# PDM.net
KiCad netlist of a schematic drawn in EAGLE
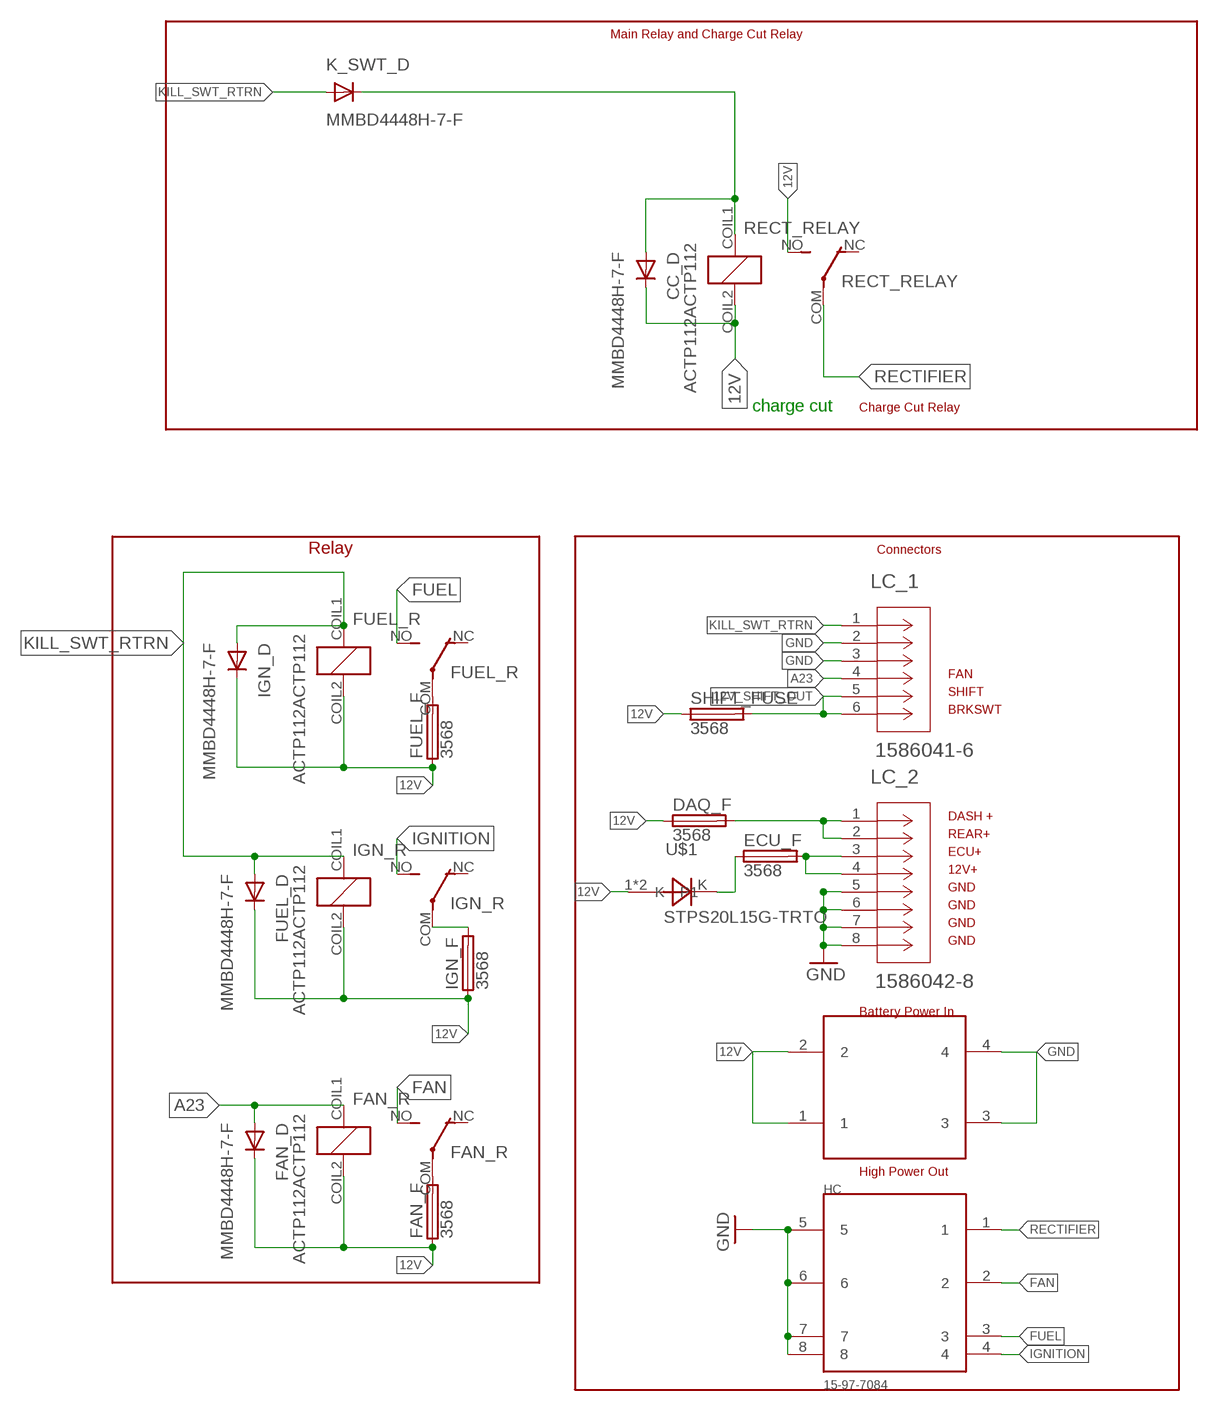
[diagram p0: schematic, sheet 1]

(export (version "E")
  (design (tool "Eeschema 10.0.6"))
  (components
    (comp (ref "BAT_SUP")
      (value "15-97-8043")
      (footprint "eagle-import:15-97-8043")
      (libsource (lib "eagle-import") (part "15-97-8043"))
    )
    (comp (ref "CC_D")
      (value "MMBD4448H-7-F")
      (footprint "eagle-import:SOT23-3")
      (libsource (lib "eagle-import") (part "MMBD4448H-7-F"))
    )
    (comp (ref "DAQ_F")
      (value "3568")
      (footprint "eagle-import:3568")
      (libsource (lib "eagle-import") (part "3568"))
    )
    (comp (ref "ECU_F")
      (value "3568")
      (footprint "eagle-import:3568")
      (libsource (lib "eagle-import") (part "3568"))
    )
    (comp (ref "FAN_D")
      (value "MMBD4448H-7-F")
      (footprint "eagle-import:SOT23-3")
      (libsource (lib "eagle-import") (part "MMBD4448H-7-F"))
    )
    (comp (ref "FAN_F")
      (value "3568")
      (footprint "eagle-import:3568")
      (libsource (lib "eagle-import") (part "3568"))
    )
    (comp (ref "FAN_R")
      (value "ACTP112ACTP112")
      (footprint "eagle-import:ACTP112")
      (libsource (lib "eagle-import") (part "ACTP112ACTP112"))
    )
    (comp (ref "FUEL_D")
      (value "MMBD4448H-7-F")
      (footprint "eagle-import:SOT23-3")
      (libsource (lib "eagle-import") (part "MMBD4448H-7-F"))
    )
    (comp (ref "FUEL_F")
      (value "3568")
      (footprint "eagle-import:3568")
      (libsource (lib "eagle-import") (part "3568"))
    )
    (comp (ref "FUEL_R")
      (value "ACTP112ACTP112")
      (footprint "eagle-import:ACTP112")
      (libsource (lib "eagle-import") (part "ACTP112ACTP112"))
    )
    (comp (ref "HC")
      (value "15-97-7084")
      (footprint "eagle-import:15-97-7084")
      (libsource (lib "eagle-import") (part "15-97-7084"))
    )
    (comp (ref "IGN_D")
      (value "MMBD4448H-7-F")
      (footprint "eagle-import:SOT23-3")
      (libsource (lib "eagle-import") (part "MMBD4448H-7-F"))
    )
    (comp (ref "IGN_F")
      (value "3568")
      (footprint "eagle-import:3568")
      (libsource (lib "eagle-import") (part "3568"))
    )
    (comp (ref "IGN_R")
      (value "ACTP112ACTP112")
      (footprint "eagle-import:ACTP112")
      (libsource (lib "eagle-import") (part "ACTP112ACTP112"))
    )
    (comp (ref "K_SWT_D")
      (value "MMBD4448H-7-F")
      (footprint "eagle-import:SOT23-3")
      (libsource (lib "eagle-import") (part "MMBD4448H-7-F"))
    )
    (comp (ref "LC_1")
      (value "1586041-6")
      (footprint "eagle-import:1586041-6")
      (libsource (lib "eagle-import") (part "1586041-6"))
    )
    (comp (ref "LC_2")
      (value "1586042-8")
      (footprint "eagle-import:1586042-8")
      (libsource (lib "eagle-import") (part "1586042-8"))
    )
    (comp (ref "RECT_RELAY")
      (value "ACTP112ACTP112")
      (footprint "eagle-import:ACTP112")
      (libsource (lib "eagle-import") (part "ACTP112ACTP112"))
    )
    (comp (ref "SHIFT_FUSE")
      (value "3568")
      (footprint "eagle-import:3568")
      (libsource (lib "eagle-import") (part "3568"))
    )
    (comp (ref "U$1")
      (value "STPS20L15G-TRTO")
      (footprint "eagle-import:TO-262DIODE")
      (libsource (lib "eagle-import") (part "STPS20L15G-TRTO"))
    )
  )
  (nets
    (net (code "1") (name "12V") (class "Default")
      (node (ref "BAT_SUP") (pin "1") (pinfunction "1_1") (pintype "bidirectional"))
      (node (ref "BAT_SUP") (pin "2") (pinfunction "2_2") (pintype "bidirectional"))
      (node (ref "CC_D") (pin "3") (pinfunction "C_3") (pintype "passive"))
      (node (ref "DAQ_F") (pin "1") (pinfunction "1_1") (pintype "passive"))
      (node (ref "DAQ_F") (pin "2") (pinfunction "1_2") (pintype "passive"))
      (node (ref "FAN_D") (pin "3") (pinfunction "C_3") (pintype "passive"))
      (node (ref "FAN_F") (pin "1") (pinfunction "1_1") (pintype "passive"))
      (node (ref "FAN_F") (pin "2") (pinfunction "1_2") (pintype "passive"))
      (node (ref "FAN_R") (pin "COIL2") (pinfunction "COIL2_COIL2") (pintype "passive"))
      (node (ref "FUEL_D") (pin "3") (pinfunction "C_3") (pintype "passive"))
      (node (ref "FUEL_F") (pin "1") (pinfunction "1_1") (pintype "passive"))
      (node (ref "FUEL_F") (pin "2") (pinfunction "1_2") (pintype "passive"))
      (node (ref "FUEL_R") (pin "COIL2") (pinfunction "COIL2_COIL2") (pintype "passive"))
      (node (ref "IGN_D") (pin "3") (pinfunction "C_3") (pintype "passive"))
      (node (ref "IGN_F") (pin "1") (pinfunction "1_1") (pintype "passive"))
      (node (ref "IGN_F") (pin "2") (pinfunction "1_2") (pintype "passive"))
      (node (ref "IGN_R") (pin "COIL2") (pinfunction "COIL2_COIL2") (pintype "passive"))
      (node (ref "RECT_RELAY") (pin "COIL2") (pinfunction "COIL2_COIL2") (pintype "passive"))
      (node (ref "RECT_RELAY") (pin "NO") (pinfunction "NO_NO") (pintype "passive"))
      (node (ref "SHIFT_FUSE") (pin "1") (pinfunction "1_1") (pintype "passive"))
      (node (ref "SHIFT_FUSE") (pin "2") (pinfunction "1_2") (pintype "passive"))
      (node (ref "U$1") (pin "1") (pinfunction "P1_1") (pintype "bidirectional"))
      (node (ref "U$1") (pin "2") (pinfunction "P1_2") (pintype "bidirectional"))
    )
    (net (code "2") (name "12V_SHIFT_OUT") (class "Default")
      (node (ref "LC_1") (pin "5") (pinfunction "5_5") (pintype "passive"))
      (node (ref "LC_1") (pin "6") (pinfunction "6_6") (pintype "passive"))
      (node (ref "SHIFT_FUSE") (pin "3") (pinfunction "2_3") (pintype "passive"))
      (node (ref "SHIFT_FUSE") (pin "4") (pinfunction "2_4") (pintype "passive"))
    )
    (net (code "3") (name "A23") (class "Default")
      (node (ref "FAN_D") (pin "1") (pinfunction "A_1") (pintype "passive"))
      (node (ref "FAN_R") (pin "COIL1") (pinfunction "COIL1_COIL1") (pintype "passive"))
      (node (ref "LC_1") (pin "4") (pinfunction "4_4") (pintype "passive"))
    )
    (net (code "4") (name "FAN") (class "Default")
      (node (ref "FAN_R") (pin "NO") (pinfunction "NO_NO") (pintype "passive"))
      (node (ref "HC") (pin "2") (pinfunction "2_2") (pintype "bidirectional"))
    )
    (net (code "5") (name "FUEL") (class "Default")
      (node (ref "FUEL_R") (pin "NO") (pinfunction "NO_NO") (pintype "passive"))
      (node (ref "HC") (pin "3") (pinfunction "3_3") (pintype "bidirectional"))
    )
    (net (code "6") (name "GND") (class "Default")
      (node (ref "BAT_SUP") (pin "3") (pinfunction "3_3") (pintype "bidirectional"))
      (node (ref "BAT_SUP") (pin "4") (pinfunction "4_4") (pintype "bidirectional"))
      (node (ref "HC") (pin "5") (pinfunction "5_5") (pintype "bidirectional"))
      (node (ref "HC") (pin "6") (pinfunction "6_6") (pintype "bidirectional"))
      (node (ref "HC") (pin "7") (pinfunction "7_7") (pintype "bidirectional"))
      (node (ref "HC") (pin "8") (pinfunction "8_8") (pintype "bidirectional"))
      (node (ref "LC_1") (pin "2") (pinfunction "2_2") (pintype "passive"))
      (node (ref "LC_1") (pin "3") (pinfunction "3_3") (pintype "passive"))
      (node (ref "LC_2") (pin "5") (pinfunction "5_5") (pintype "passive"))
      (node (ref "LC_2") (pin "6") (pinfunction "6_6") (pintype "passive"))
      (node (ref "LC_2") (pin "7") (pinfunction "7_7") (pintype "passive"))
      (node (ref "LC_2") (pin "8") (pinfunction "8_8") (pintype "passive"))
    )
    (net (code "7") (name "IGNITION") (class "Default")
      (node (ref "HC") (pin "4") (pinfunction "4_4") (pintype "bidirectional"))
      (node (ref "IGN_R") (pin "NO") (pinfunction "NO_NO") (pintype "passive"))
    )
    (net (code "8") (name "KILL_SWT_RTRN") (class "Default")
      (node (ref "FUEL_D") (pin "1") (pinfunction "A_1") (pintype "passive"))
      (node (ref "FUEL_R") (pin "COIL1") (pinfunction "COIL1_COIL1") (pintype "passive"))
      (node (ref "IGN_D") (pin "1") (pinfunction "A_1") (pintype "passive"))
      (node (ref "IGN_R") (pin "COIL1") (pinfunction "COIL1_COIL1") (pintype "passive"))
      (node (ref "K_SWT_D") (pin "1") (pinfunction "A_1") (pintype "passive"))
      (node (ref "LC_1") (pin "1") (pinfunction "1_1") (pintype "passive"))
    )
    (net (code "9") (name "Net-(CC_D-A)") (class "Default")
      (node (ref "CC_D") (pin "1") (pinfunction "A_1") (pintype "passive"))
      (node (ref "K_SWT_D") (pin "3") (pinfunction "C_3") (pintype "passive"))
      (node (ref "RECT_RELAY") (pin "COIL1") (pinfunction "COIL1_COIL1") (pintype "passive"))
    )
    (net (code "10") (name "Net-(DAQ_F-2-Pad3)") (class "Default")
      (node (ref "DAQ_F") (pin "3") (pinfunction "2_3") (pintype "passive"))
      (node (ref "DAQ_F") (pin "4") (pinfunction "2_4") (pintype "passive"))
      (node (ref "LC_2") (pin "1") (pinfunction "1_1") (pintype "passive"))
      (node (ref "LC_2") (pin "2") (pinfunction "2_2") (pintype "passive"))
    )
    (net (code "11") (name "Net-(ECU_F-1-Pad2)") (class "Default")
      (node (ref "ECU_F") (pin "1") (pinfunction "1_1") (pintype "passive"))
      (node (ref "ECU_F") (pin "2") (pinfunction "1_2") (pintype "passive"))
      (node (ref "U$1") (pin "K") (pinfunction "K_K") (pintype "bidirectional"))
    )
    (net (code "12") (name "Net-(ECU_F-2-Pad3)") (class "Default")
      (node (ref "ECU_F") (pin "3") (pinfunction "2_3") (pintype "passive"))
      (node (ref "ECU_F") (pin "4") (pinfunction "2_4") (pintype "passive"))
      (node (ref "LC_2") (pin "3") (pinfunction "3_3") (pintype "passive"))
      (node (ref "LC_2") (pin "4") (pinfunction "4_4") (pintype "passive"))
    )
    (net (code "13") (name "Net-(FAN_F-2-Pad3)") (class "Default")
      (node (ref "FAN_F") (pin "3") (pinfunction "2_3") (pintype "passive"))
      (node (ref "FAN_F") (pin "4") (pinfunction "2_4") (pintype "passive"))
      (node (ref "FAN_R") (pin "COM") (pinfunction "COM_COM") (pintype "passive"))
    )
    (net (code "14") (name "Net-(FUEL_F-2-Pad3)") (class "Default")
      (node (ref "FUEL_F") (pin "3") (pinfunction "2_3") (pintype "passive"))
      (node (ref "FUEL_F") (pin "4") (pinfunction "2_4") (pintype "passive"))
      (node (ref "FUEL_R") (pin "COM") (pinfunction "COM_COM") (pintype "passive"))
    )
    (net (code "15") (name "Net-(IGN_F-2-Pad3)") (class "Default")
      (node (ref "IGN_F") (pin "3") (pinfunction "2_3") (pintype "passive"))
      (node (ref "IGN_F") (pin "4") (pinfunction "2_4") (pintype "passive"))
      (node (ref "IGN_R") (pin "COM") (pinfunction "COM_COM") (pintype "passive"))
    )
    (net (code "16") (name "RECTIFIER") (class "Default")
      (node (ref "HC") (pin "1") (pinfunction "1_1") (pintype "bidirectional"))
      (node (ref "RECT_RELAY") (pin "COM") (pinfunction "COM_COM") (pintype "passive"))
    )
    (net (code "17") (name "unconnected-(FAN_R-PadNC)") (class "Default")
      (node (ref "FAN_R") (pin "NC") (pinfunction "NC_NC") (pintype "passive"))
    )
    (net (code "18") (name "unconnected-(FUEL_R-PadNC)") (class "Default")
      (node (ref "FUEL_R") (pin "NC") (pinfunction "NC_NC") (pintype "passive"))
    )
    (net (code "19") (name "unconnected-(IGN_R-PadNC)") (class "Default")
      (node (ref "IGN_R") (pin "NC") (pinfunction "NC_NC") (pintype "passive"))
    )
    (net (code "20") (name "unconnected-(RECT_RELAY-PadNC)") (class "Default")
      (node (ref "RECT_RELAY") (pin "NC") (pinfunction "NC_NC") (pintype "passive"))
    )
  )
)
